# sdadapter.net
KiCad netlist of a schematic drawn in EAGLE
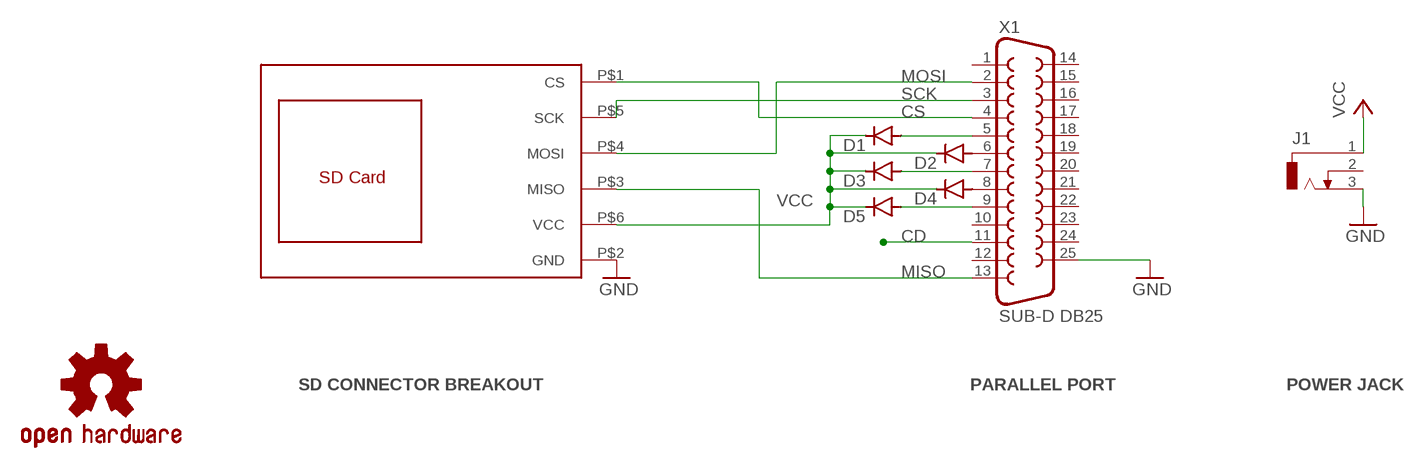
[diagram p0: schematic, sheet 1]

(export (version "E")
  (design (tool "Eeschema 10.0.6"))
  (components
    (comp (ref "D1")
      (value "CGRM4001-G")
      (footprint "eagle-import:SOD-123_MINI-SMA")
      (libsource (lib "eagle-import") (part "CGRM400-G1"))
    )
    (comp (ref "D2")
      (value "CGRM4001-G")
      (footprint "eagle-import:SOD-123_MINI-SMA")
      (libsource (lib "eagle-import") (part "CGRM400-G1"))
    )
    (comp (ref "D3")
      (value "CGRM4001-G")
      (footprint "eagle-import:SOD-123_MINI-SMA")
      (libsource (lib "eagle-import") (part "CGRM400-G1"))
    )
    (comp (ref "D4")
      (value "CGRM4001-G")
      (footprint "eagle-import:SOD-123_MINI-SMA")
      (libsource (lib "eagle-import") (part "CGRM400-G1"))
    )
    (comp (ref "D5")
      (value "CGRM4001-G")
      (footprint "eagle-import:SOD-123_MINI-SMA")
      (libsource (lib "eagle-import") (part "CGRM400-G1"))
    )
    (comp (ref "J1")
      (value "DCJ0303")
      (footprint "eagle-import:DCJ0303")
      (libsource (lib "eagle-import") (part "DCJ0303"))
    )
    (comp (ref "LOGO2")
      (value "OSHW-LOGOS")
      (footprint "eagle-import:OSHW-LOGO-S")
      (libsource (lib "eagle-import") (part "OSHW-LOGOS"))
    )
    (comp (ref "U$1")
      (value "SD_ADAPTER")
      (footprint "eagle-import:DEBO_MICRO_SD")
      (libsource (lib "eagle-import") (part "SD_ADAPTER"))
    )
    (comp (ref "X1")
      (value "SUB-D DB25")
      (footprint "eagle-import:F25D")
      (libsource (lib "eagle-import") (part "F25D"))
    )
  )
  (nets
    (net (code "1") (name "/CD") (class "Default")
      (node (ref "X1") (pin "11") (pinfunction "11_11") (pintype "passive"))
    )
    (net (code "2") (name "/CS") (class "Default")
      (node (ref "U$1") (pin "P$1") (pinfunction "CS_P$1") (pintype "bidirectional"))
      (node (ref "X1") (pin "4") (pinfunction "4_4") (pintype "passive"))
    )
    (net (code "3") (name "/MISO") (class "Default")
      (node (ref "U$1") (pin "P$3") (pinfunction "MISO_P$3") (pintype "bidirectional"))
      (node (ref "X1") (pin "13") (pinfunction "13_13") (pintype "passive"))
    )
    (net (code "4") (name "/MOSI") (class "Default")
      (node (ref "U$1") (pin "P$4") (pinfunction "MOSI_P$4") (pintype "bidirectional"))
      (node (ref "X1") (pin "2") (pinfunction "2_2") (pintype "passive"))
    )
    (net (code "5") (name "/SCK") (class "Default")
      (node (ref "U$1") (pin "P$5") (pinfunction "SCK_P$5") (pintype "bidirectional"))
      (node (ref "X1") (pin "3") (pinfunction "3_3") (pintype "passive"))
    )
    (net (code "6") (name "GND") (class "Default")
      (node (ref "J1") (pin "3") (pinfunction "3_3") (pintype "passive"))
      (node (ref "U$1") (pin "P$2") (pinfunction "GND_P$2") (pintype "bidirectional"))
      (node (ref "X1") (pin "25") (pinfunction "25_25") (pintype "passive"))
    )
    (net (code "7") (name "Net-(D1-PadA)") (class "Default")
      (node (ref "D1") (pin "A") (pinfunction "A_A") (pintype "passive"))
      (node (ref "X1") (pin "5") (pinfunction "5_5") (pintype "passive"))
    )
    (net (code "8") (name "Net-(D2-PadA)") (class "Default")
      (node (ref "D2") (pin "A") (pinfunction "A_A") (pintype "passive"))
      (node (ref "X1") (pin "6") (pinfunction "6_6") (pintype "passive"))
    )
    (net (code "9") (name "Net-(D3-PadA)") (class "Default")
      (node (ref "D3") (pin "A") (pinfunction "A_A") (pintype "passive"))
      (node (ref "X1") (pin "7") (pinfunction "7_7") (pintype "passive"))
    )
    (net (code "10") (name "Net-(D4-PadA)") (class "Default")
      (node (ref "D4") (pin "A") (pinfunction "A_A") (pintype "passive"))
      (node (ref "X1") (pin "8") (pinfunction "8_8") (pintype "passive"))
    )
    (net (code "11") (name "Net-(D5-PadA)") (class "Default")
      (node (ref "D5") (pin "A") (pinfunction "A_A") (pintype "passive"))
      (node (ref "X1") (pin "9") (pinfunction "9_9") (pintype "passive"))
    )
    (net (code "12") (name "VCC") (class "Default")
      (node (ref "D1") (pin "C") (pinfunction "C_C") (pintype "passive"))
      (node (ref "D2") (pin "C") (pinfunction "C_C") (pintype "passive"))
      (node (ref "D3") (pin "C") (pinfunction "C_C") (pintype "passive"))
      (node (ref "D4") (pin "C") (pinfunction "C_C") (pintype "passive"))
      (node (ref "D5") (pin "C") (pinfunction "C_C") (pintype "passive"))
      (node (ref "J1") (pin "1") (pinfunction "1_1") (pintype "passive"))
      (node (ref "U$1") (pin "P$6") (pinfunction "VCC_P$6") (pintype "bidirectional"))
    )
    (net (code "13") (name "unconnected-(J1-Pad2)") (class "Default")
      (node (ref "J1") (pin "2") (pinfunction "2_2") (pintype "passive"))
    )
    (net (code "14") (name "unconnected-(X1-Pad1)") (class "Default")
      (node (ref "X1") (pin "1") (pinfunction "1_1") (pintype "passive"))
    )
    (net (code "15") (name "unconnected-(X1-Pad10)") (class "Default")
      (node (ref "X1") (pin "10") (pinfunction "10_10") (pintype "passive"))
    )
    (net (code "16") (name "unconnected-(X1-Pad12)") (class "Default")
      (node (ref "X1") (pin "12") (pinfunction "12_12") (pintype "passive"))
    )
    (net (code "17") (name "unconnected-(X1-Pad14)") (class "Default")
      (node (ref "X1") (pin "14") (pinfunction "14_14") (pintype "passive"))
    )
    (net (code "18") (name "unconnected-(X1-Pad15)") (class "Default")
      (node (ref "X1") (pin "15") (pinfunction "15_15") (pintype "passive"))
    )
    (net (code "19") (name "unconnected-(X1-Pad16)") (class "Default")
      (node (ref "X1") (pin "16") (pinfunction "16_16") (pintype "passive"))
    )
    (net (code "20") (name "unconnected-(X1-Pad17)") (class "Default")
      (node (ref "X1") (pin "17") (pinfunction "17_17") (pintype "passive"))
    )
    (net (code "21") (name "unconnected-(X1-Pad18)") (class "Default")
      (node (ref "X1") (pin "18") (pinfunction "18_18") (pintype "passive"))
    )
    (net (code "22") (name "unconnected-(X1-Pad19)") (class "Default")
      (node (ref "X1") (pin "19") (pinfunction "19_19") (pintype "passive"))
    )
    (net (code "23") (name "unconnected-(X1-Pad20)") (class "Default")
      (node (ref "X1") (pin "20") (pinfunction "20_20") (pintype "passive"))
    )
    (net (code "24") (name "unconnected-(X1-Pad21)") (class "Default")
      (node (ref "X1") (pin "21") (pinfunction "21_21") (pintype "passive"))
    )
    (net (code "25") (name "unconnected-(X1-Pad22)") (class "Default")
      (node (ref "X1") (pin "22") (pinfunction "22_22") (pintype "passive"))
    )
    (net (code "26") (name "unconnected-(X1-Pad23)") (class "Default")
      (node (ref "X1") (pin "23") (pinfunction "23_23") (pintype "passive"))
    )
    (net (code "27") (name "unconnected-(X1-Pad24)") (class "Default")
      (node (ref "X1") (pin "24") (pinfunction "24_24") (pintype "passive"))
    )
  )
)
